# Sheet1.net
KiCad netlist of a schematic drawn in Altium Designer
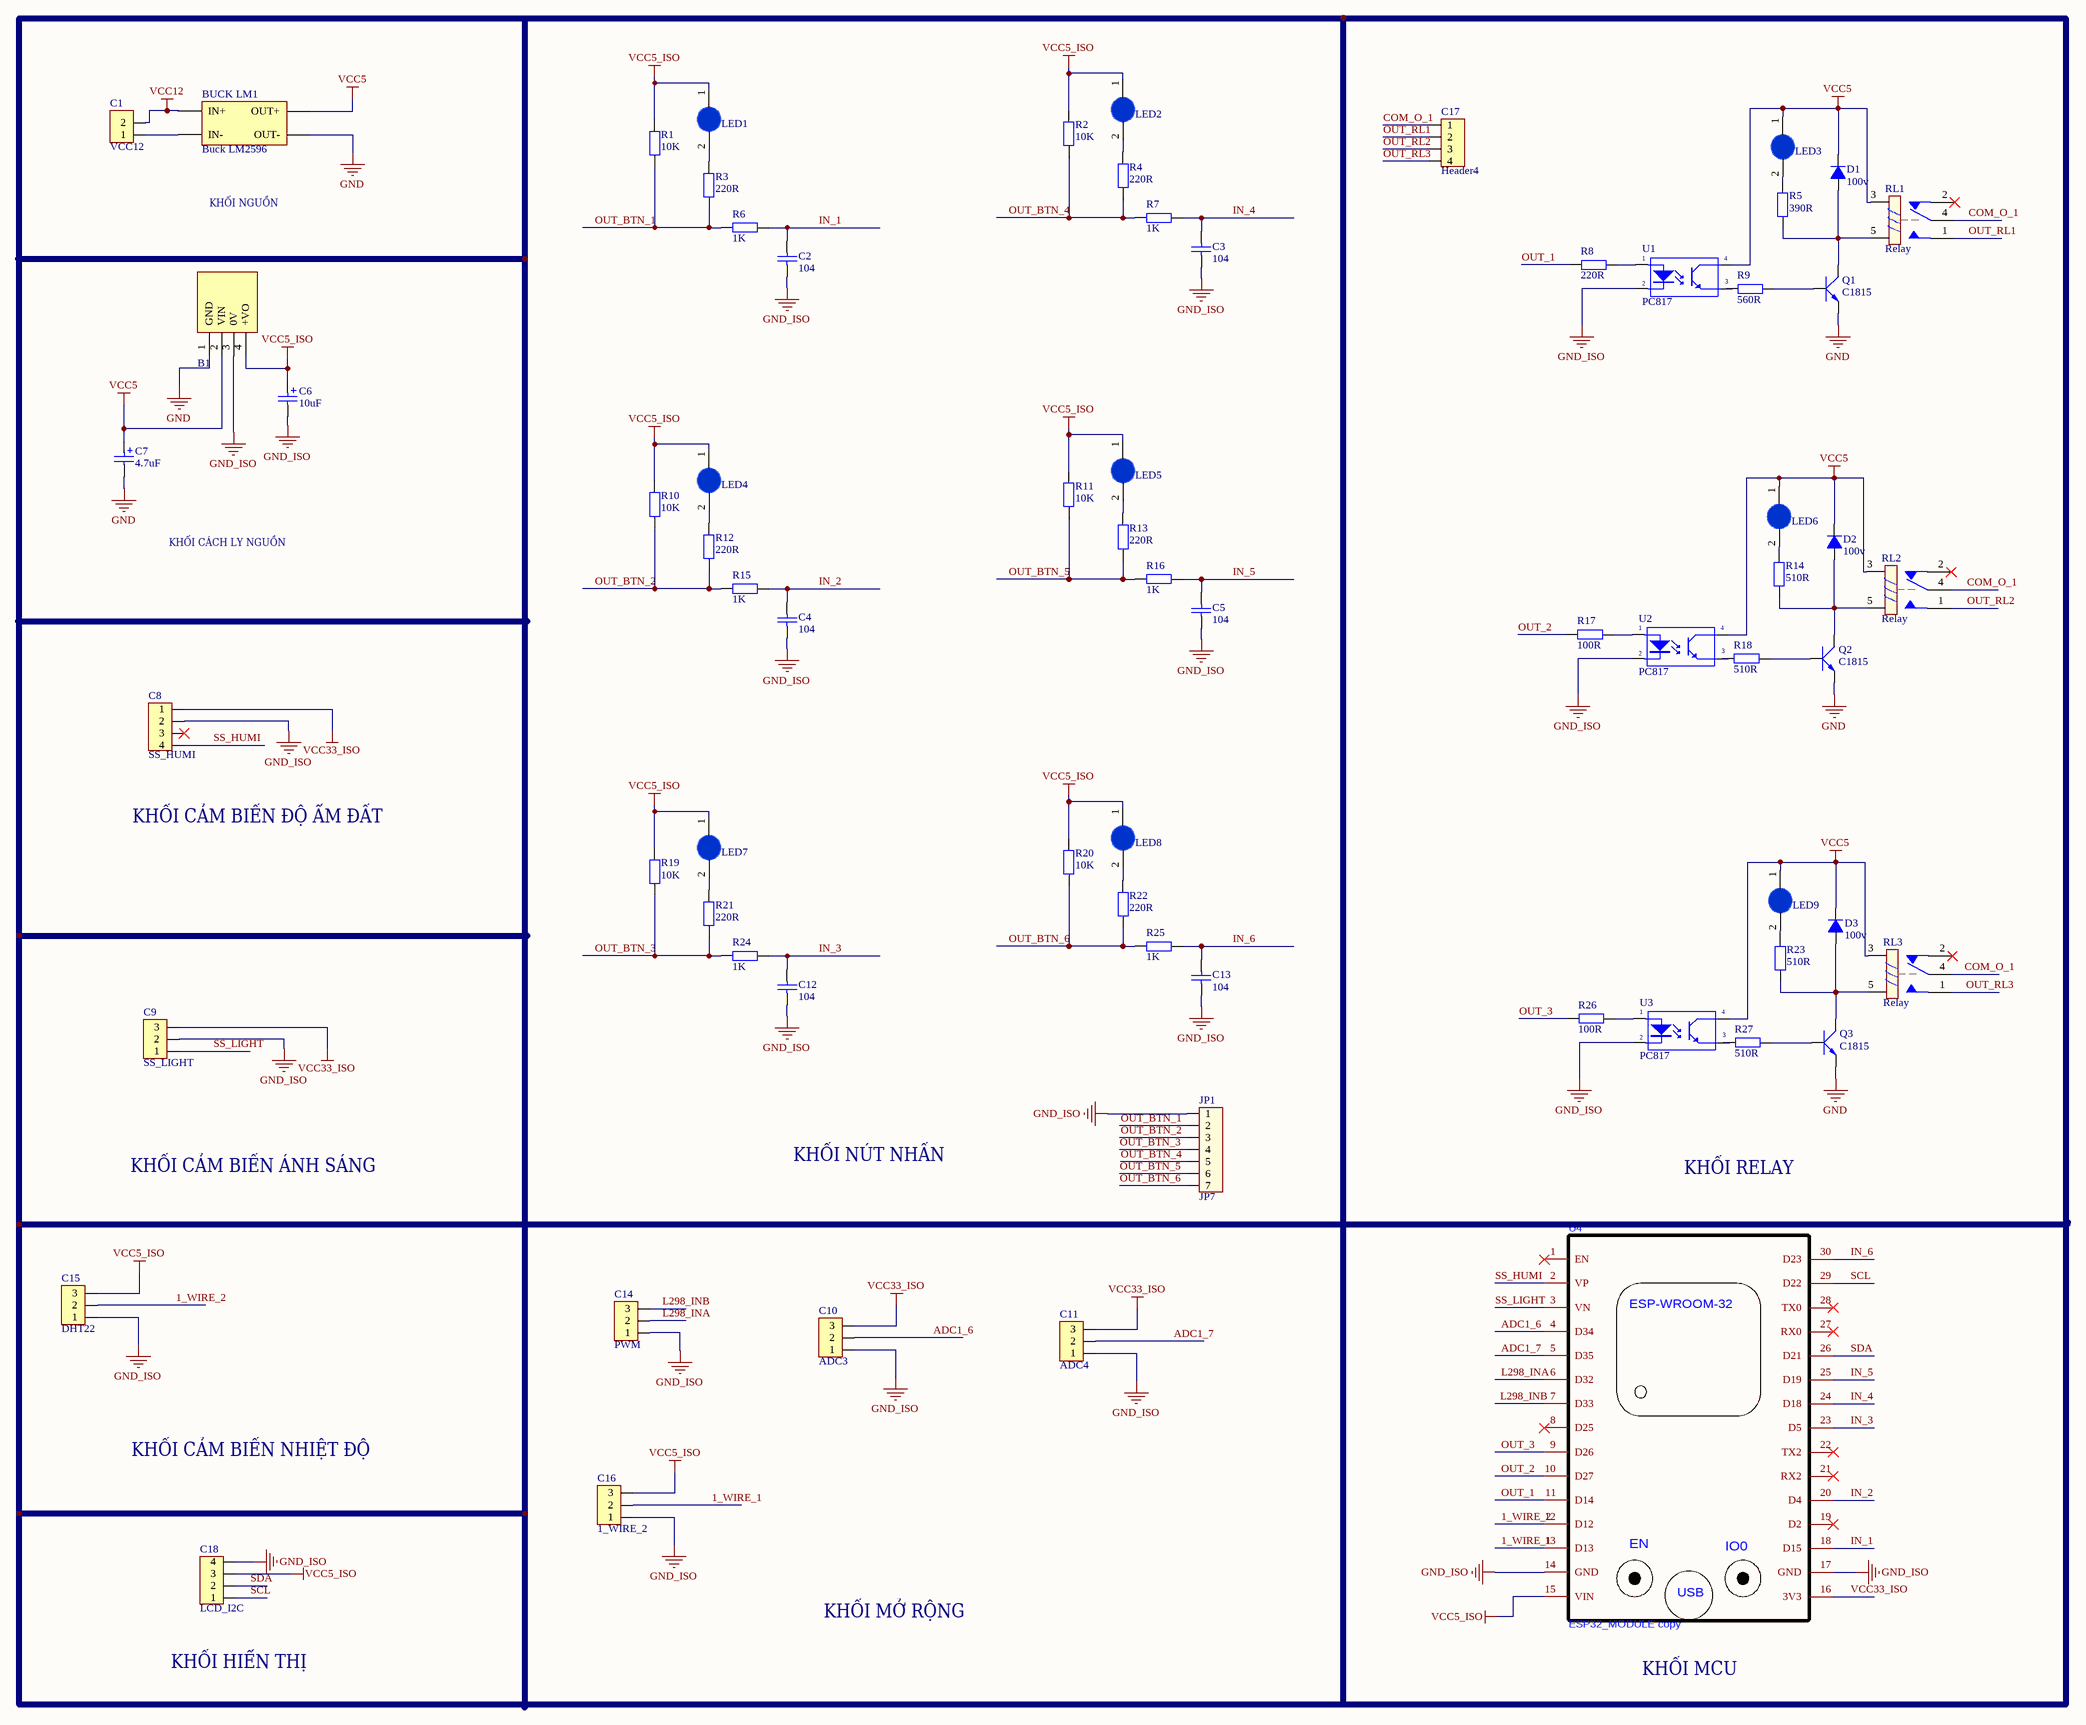
[diagram p0: Sheet1.SchDoc]

(export (version "E")
  (design (tool "Eeschema 10.0.6"))
  (components
    (comp (ref "B1")
      (value "B0505S1W")
      (footprint "B0505S1W")
      (description "Power Supply")
      (fields (field (name "MANUFACTURER_PART_NUMBER") "B0505S-1W"))
      (libsource (lib "myLib_v1") (part "B0505S1W"))
    )
    (comp (ref "BUCK LM1")
      (value "Buck LM2596")
      (footprint "BUCK LM2596")
      (libsource (lib "myLib_v1") (part "Buck LM2596"))
    )
    (comp (ref "C1")
      (value "VCC12")
      (footprint "Header2")
      (description "Header IDC, 2 x 1 Pin Vertical 2.54mm Pitch (Non-Boxed, Male)")
      (fields
        (field (name "MANUFACTURER") "Würth Elektronik eiSos GmbH")
        (field (name "PARTNO") "613002143121")
        (field (name "CREATED BY") "Karrer Zheng")
      )
      (libsource (lib "myLib_v1") (part "Header2"))
    )
    (comp (ref "C2")
      (value "104")
      (footprint "tu gom")
      (description "Cắm")
      (libsource (lib "Altium_Lib_by_KhueNguyenCreator") (part "Tu gom 104 50V"))
    )
    (comp (ref "C3")
      (value "104")
      (footprint "tu gom")
      (description "Cắm")
      (libsource (lib "Altium_Lib_by_KhueNguyenCreator") (part "Tu gom 104 50V"))
    )
    (comp (ref "C4")
      (value "104")
      (footprint "tu gom")
      (description "Cắm")
      (libsource (lib "Altium_Lib_by_KhueNguyenCreator") (part "Tu gom 104 50V"))
    )
    (comp (ref "C5")
      (value "104")
      (footprint "tu gom")
      (description "Cắm")
      (libsource (lib "Altium_Lib_by_KhueNguyenCreator") (part "Tu gom 104 50V"))
    )
    (comp (ref "C6")
      (value "10uF")
      (footprint "CP2/5")
      (description "Polarized Capacitor (Surface Mount)")
      (fields (field (name "Comment") "Cap Pol3") (field (name "PUBLISHER") "Altium Limited"))
      (libsource (lib "myLib_v1") (part "Cap Pol3"))
    )
    (comp (ref "C7")
      (value "4.7uF")
      (footprint "CP2/5")
      (description "Polarized Capacitor (Surface Mount)")
      (fields (field (name "Comment") "Cap Pol3") (field (name "PUBLISHER") "Altium Limited"))
      (libsource (lib "myLib_v1") (part "Cap Pol3"))
    )
    (comp (ref "C8")
      (value "SS_HUMI")
      (footprint "Header4")
      (description "Header IDC, 4 x 1 Pin Vertical 2.54mm Pitch (Non-Boxed, Male)")
      (fields
        (field (name "MANUFACTURER") "Würth Elektronik eiSos GmbH")
        (field (name "PARTNO") "613002143121")
        (field (name "CREATED BY") "Karrer Zheng")
      )
      (libsource (lib "myLib_v1") (part "Header4"))
    )
    (comp (ref "C9")
      (value "SS_LIGHT")
      (footprint "Header3")
      (description "Header IDC, 3 x 1 Pin Vertical 2.54mm Pitch (Non-Boxed, Male)")
      (fields
        (field (name "MANUFACTURER") "Würth Elektronik eiSos GmbH")
        (field (name "PARTNO") "613002143121")
        (field (name "CREATED BY") "Karrer Zheng")
      )
      (libsource (lib "myLib_v1") (part "Header3"))
    )
    (comp (ref "C10")
      (value "ADC3")
      (footprint "Header3")
      (description "Header IDC, 3 x 1 Pin Vertical 2.54mm Pitch (Non-Boxed, Male)")
      (fields
        (field (name "MANUFACTURER") "Würth Elektronik eiSos GmbH")
        (field (name "PARTNO") "613002143121")
        (field (name "CREATED BY") "Karrer Zheng")
      )
      (libsource (lib "myLib_v1") (part "Header3"))
    )
    (comp (ref "C11")
      (value "ADC4")
      (footprint "Header3")
      (description "Header IDC, 3 x 1 Pin Vertical 2.54mm Pitch (Non-Boxed, Male)")
      (fields
        (field (name "MANUFACTURER") "Würth Elektronik eiSos GmbH")
        (field (name "PARTNO") "613002143121")
        (field (name "CREATED BY") "Karrer Zheng")
      )
      (libsource (lib "myLib_v1") (part "Header3"))
    )
    (comp (ref "C12")
      (value "104")
      (footprint "tu gom")
      (description "Cắm")
      (libsource (lib "Altium_Lib_by_KhueNguyenCreator") (part "Tu gom 104 50V"))
    )
    (comp (ref "C13")
      (value "104")
      (footprint "tu gom")
      (description "Cắm")
      (libsource (lib "Altium_Lib_by_KhueNguyenCreator") (part "Tu gom 104 50V"))
    )
    (comp (ref "C14")
      (value "PWM")
      (footprint "Header3")
      (description "Header IDC, 3 x 1 Pin Vertical 2.54mm Pitch (Non-Boxed, Male)")
      (fields
        (field (name "MANUFACTURER") "Würth Elektronik eiSos GmbH")
        (field (name "PARTNO") "613002143121")
        (field (name "CREATED BY") "Karrer Zheng")
      )
      (libsource (lib "myLib_v1") (part "Header3"))
    )
    (comp (ref "C15")
      (value "DHT22")
      (footprint "Header3")
      (description "Header IDC, 3 x 1 Pin Vertical 2.54mm Pitch (Non-Boxed, Male)")
      (fields
        (field (name "MANUFACTURER") "Würth Elektronik eiSos GmbH")
        (field (name "PARTNO") "613002143121")
        (field (name "CREATED BY") "Karrer Zheng")
      )
      (libsource (lib "myLib_v1") (part "Header3"))
    )
    (comp (ref "C16")
      (value "1_WIRE_2")
      (footprint "Header3")
      (description "Header IDC, 3 x 1 Pin Vertical 2.54mm Pitch (Non-Boxed, Male)")
      (fields
        (field (name "MANUFACTURER") "Würth Elektronik eiSos GmbH")
        (field (name "PARTNO") "613002143121")
        (field (name "CREATED BY") "Karrer Zheng")
      )
      (libsource (lib "myLib_v1") (part "Header3"))
    )
    (comp (ref "C17")
      (value "Header4")
      (footprint "Header4")
      (description "Header IDC, 4 x 1 Pin Vertical 2.54mm Pitch (Non-Boxed, Male)")
      (fields
        (field (name "MANUFACTURER") "Würth Elektronik eiSos GmbH")
        (field (name "PARTNO") "613002143121")
        (field (name "CREATED BY") "Karrer Zheng")
      )
      (libsource (lib "") (part "Header4_1"))
    )
    (comp (ref "C18")
      (value "LCD_I2C")
      (footprint "Header4")
      (description "Header IDC, 4 x 1 Pin Vertical 2.54mm Pitch (Non-Boxed, Male)")
      (fields
        (field (name "MANUFACTURER") "Würth Elektronik eiSos GmbH")
        (field (name "PARTNO") "613002143121")
        (field (name "CREATED BY") "Karrer Zheng")
      )
      (libsource (lib "") (part "Header4_2"))
    )
    (comp (ref "D1")
      (value "100v")
      (footprint "DIODE 0.5A")
      (description "Cắm")
      (libsource (lib "Altium_Lib_by_KhueNguyenCreator") (part "Diode 1N4148"))
    )
    (comp (ref "D2")
      (value "100v")
      (footprint "DIODE 0.5A")
      (description "Cắm")
      (libsource (lib "Altium_Lib_by_KhueNguyenCreator") (part "Diode 1N4148"))
    )
    (comp (ref "D3")
      (value "100v")
      (footprint "DIODE 0.5A")
      (description "Cắm")
      (libsource (lib "Altium_Lib_by_KhueNguyenCreator") (part "Diode 1N4148"))
    )
    (comp (ref "JP1")
      (value "JP7")
      (footprint "Header7")
      (description "Connector 7")
      (libsource (lib "myLib_v1") (part "Header7"))
    )
    (comp (ref "LED1")
      (value "LED 3mm")
      (footprint "LED-3MM-BLUE")
      (description "Cắm")
      (libsource (lib "myLib_v1") (part "LED 3mm Xanh Duong"))
    )
    (comp (ref "LED2")
      (value "LED 3mm")
      (footprint "LED-3MM-BLUE")
      (description "Cắm")
      (libsource (lib "myLib_v1") (part "LED 3mm Xanh Duong"))
    )
    (comp (ref "LED3")
      (value "LED 3mm")
      (footprint "LED-3MM-BLUE")
      (description "Cắm")
      (libsource (lib "myLib_v1") (part "LED 3mm Xanh Duong"))
    )
    (comp (ref "LED4")
      (value "LED 3mm")
      (footprint "LED-3MM-BLUE")
      (description "Cắm")
      (libsource (lib "myLib_v1") (part "LED 3mm Xanh Duong"))
    )
    (comp (ref "LED5")
      (value "LED 3mm")
      (footprint "LED-3MM-BLUE")
      (description "Cắm")
      (libsource (lib "myLib_v1") (part "LED 3mm Xanh Duong"))
    )
    (comp (ref "LED6")
      (value "LED 3mm")
      (footprint "LED-3MM-BLUE")
      (description "Cắm")
      (libsource (lib "myLib_v1") (part "LED 3mm Xanh Duong"))
    )
    (comp (ref "LED7")
      (value "LED 3mm")
      (footprint "LED-3MM-BLUE")
      (description "Cắm")
      (libsource (lib "myLib_v1") (part "LED 3mm Xanh Duong"))
    )
    (comp (ref "LED8")
      (value "LED 3mm")
      (footprint "LED-3MM-BLUE")
      (description "Cắm")
      (libsource (lib "myLib_v1") (part "LED 3mm Xanh Duong"))
    )
    (comp (ref "LED9")
      (value "LED 3mm")
      (footprint "LED-3MM-BLUE")
      (description "Cắm")
      (libsource (lib "myLib_v1") (part "LED 3mm Xanh Duong"))
    )
    (comp (ref "Q1")
      (value "C1815")
      (footprint "C1815_cam")
      (description "NPN 600mW, ECB")
      (libsource (lib "myLib_v1") (part "C1815"))
    )
    (comp (ref "Q2")
      (value "C1815")
      (footprint "C1815_cam")
      (description "NPN 600mW, ECB")
      (libsource (lib "myLib_v1") (part "C1815"))
    )
    (comp (ref "Q3")
      (value "C1815")
      (footprint "C1815_cam")
      (description "NPN 600mW, ECB")
      (libsource (lib "myLib_v1") (part "C1815"))
    )
    (comp (ref "R1")
      (value "10K")
      (footprint "R1/4W")
      (description "Resistor 1/4W")
      (libsource (lib "myLib_v1") (part "R1/4W"))
    )
    (comp (ref "R2")
      (value "10K")
      (footprint "R1/4W")
      (description "Resistor 1/4W")
      (libsource (lib "myLib_v1") (part "R1/4W"))
    )
    (comp (ref "R3")
      (value "220R")
      (footprint "R1/4W")
      (description "Resistor 1/4W")
      (libsource (lib "myLib_v1") (part "R1/4W"))
    )
    (comp (ref "R4")
      (value "220R")
      (footprint "R1/4W")
      (description "Resistor 1/4W")
      (libsource (lib "myLib_v1") (part "R1/4W"))
    )
    (comp (ref "R5")
      (value "390R")
      (footprint "R1/4W")
      (description "Resistor 1/4W")
      (libsource (lib "myLib_v1") (part "R1/4W"))
    )
    (comp (ref "R6")
      (value "1K")
      (footprint "R1/4W")
      (description "Resistor 1/4W")
      (libsource (lib "myLib_v1") (part "R1/4W"))
    )
    (comp (ref "R7")
      (value "1K")
      (footprint "R1/4W")
      (description "Resistor 1/4W")
      (libsource (lib "myLib_v1") (part "R1/4W"))
    )
    (comp (ref "R8")
      (value "220R")
      (footprint "R1/4W")
      (description "Resistor 1/4W")
      (libsource (lib "myLib_v1") (part "R1/4W"))
    )
    (comp (ref "R9")
      (value "560R")
      (footprint "R1/4W")
      (description "Resistor 1/4W")
      (libsource (lib "myLib_v1") (part "R1/4W"))
    )
    (comp (ref "R10")
      (value "10K")
      (footprint "R1/4W")
      (description "Resistor 1/4W")
      (libsource (lib "myLib_v1") (part "R1/4W"))
    )
    (comp (ref "R11")
      (value "10K")
      (footprint "R1/4W")
      (description "Resistor 1/4W")
      (libsource (lib "myLib_v1") (part "R1/4W"))
    )
    (comp (ref "R12")
      (value "220R")
      (footprint "R1/4W")
      (description "Resistor 1/4W")
      (libsource (lib "myLib_v1") (part "R1/4W"))
    )
    (comp (ref "R13")
      (value "220R")
      (footprint "R1/4W")
      (description "Resistor 1/4W")
      (libsource (lib "myLib_v1") (part "R1/4W"))
    )
    (comp (ref "R14")
      (value "510R")
      (footprint "R1/4W")
      (description "Resistor 1/4W")
      (libsource (lib "myLib_v1") (part "R1/4W"))
    )
    (comp (ref "R15")
      (value "1K")
      (footprint "R1/4W")
      (description "Resistor 1/4W")
      (libsource (lib "myLib_v1") (part "R1/4W"))
    )
    (comp (ref "R16")
      (value "1K")
      (footprint "R1/4W")
      (description "Resistor 1/4W")
      (libsource (lib "myLib_v1") (part "R1/4W"))
    )
    (comp (ref "R17")
      (value "100R")
      (footprint "R1/4W")
      (description "Resistor 1/4W")
      (libsource (lib "myLib_v1") (part "R1/4W"))
    )
    (comp (ref "R18")
      (value "510R")
      (footprint "R1/4W")
      (description "Resistor 1/4W")
      (libsource (lib "myLib_v1") (part "R1/4W"))
    )
    (comp (ref "R19")
      (value "10K")
      (footprint "R1/4W")
      (description "Resistor 1/4W")
      (libsource (lib "myLib_v1") (part "R1/4W"))
    )
    (comp (ref "R20")
      (value "10K")
      (footprint "R1/4W")
      (description "Resistor 1/4W")
      (libsource (lib "myLib_v1") (part "R1/4W"))
    )
    (comp (ref "R21")
      (value "220R")
      (footprint "R1/4W")
      (description "Resistor 1/4W")
      (libsource (lib "myLib_v1") (part "R1/4W"))
    )
    (comp (ref "R22")
      (value "220R")
      (footprint "R1/4W")
      (description "Resistor 1/4W")
      (libsource (lib "myLib_v1") (part "R1/4W"))
    )
    (comp (ref "R23")
      (value "510R")
      (footprint "R1/4W")
      (description "Resistor 1/4W")
      (libsource (lib "myLib_v1") (part "R1/4W"))
    )
    (comp (ref "R24")
      (value "1K")
      (footprint "R1/4W")
      (description "Resistor 1/4W")
      (libsource (lib "myLib_v1") (part "R1/4W"))
    )
    (comp (ref "R25")
      (value "1K")
      (footprint "R1/4W")
      (description "Resistor 1/4W")
      (libsource (lib "myLib_v1") (part "R1/4W"))
    )
    (comp (ref "R26")
      (value "100R")
      (footprint "R1/4W")
      (description "Resistor 1/4W")
      (libsource (lib "myLib_v1") (part "R1/4W"))
    )
    (comp (ref "R27")
      (value "510R")
      (footprint "R1/4W")
      (description "Resistor 1/4W")
      (libsource (lib "myLib_v1") (part "R1/4W"))
    )
    (comp (ref "RL1")
      (value "Relay")
      (footprint "RELAY_SRA_05VDC_SL_C")
      (description "Relay 5 Chan")
      (libsource (lib "myLib_v1") (part "RL_SRA-05VDC-SL-C"))
    )
    (comp (ref "RL2")
      (value "Relay")
      (footprint "RELAY_SRA_05VDC_SL_C")
      (description "Relay 5 Chan")
      (libsource (lib "myLib_v1") (part "RL_SRA-05VDC-SL-C"))
    )
    (comp (ref "RL3")
      (value "Relay")
      (footprint "RELAY_SRA_05VDC_SL_C")
      (description "Relay 5 Chan")
      (libsource (lib "myLib_v1") (part "RL_SRA-05VDC-SL-C"))
    )
    (comp (ref "U1")
      (value "PC817")
      (footprint "DIP4/W0.3")
      (description "Single Opto")
      (libsource (lib "myLib_v1") (part "PC817"))
    )
    (comp (ref "U2")
      (value "PC817")
      (footprint "DIP4/W0.3")
      (description "Single Opto")
      (libsource (lib "myLib_v1") (part "PC817"))
    )
    (comp (ref "U3")
      (value "PC817")
      (footprint "DIP4/W0.3")
      (description "Single Opto")
      (libsource (lib "myLib_v1") (part "PC817"))
    )
    (comp (ref "U4")
      (value "ESP32_MODULE copy")
      (footprint "ESP32-WIFIMODULE-FOOTPRINT")
      (libsource (lib "myLib_v1") (part "ESP32_MODULE copy"))
    )
  )
  (nets
    (net (code "1") (name "/1_WIRE_1") (class "Default")
      (node (ref "C16") (pin "2") (pinfunction "2_2") (pintype "passive"))
      (node (ref "U4") (pin "13") (pinfunction "D13_13") (pintype "passive"))
    )
    (net (code "2") (name "/1_WIRE_2") (class "Default")
      (node (ref "C15") (pin "2") (pinfunction "2_2") (pintype "passive"))
      (node (ref "U4") (pin "12") (pinfunction "D12_12") (pintype "passive"))
    )
    (net (code "3") (name "/ADC1_6") (class "Default")
      (node (ref "C10") (pin "2") (pinfunction "2_2") (pintype "passive"))
      (node (ref "U4") (pin "4") (pinfunction "D34_4") (pintype "passive"))
    )
    (net (code "4") (name "/ADC1_7") (class "Default")
      (node (ref "C11") (pin "2") (pinfunction "2_2") (pintype "passive"))
      (node (ref "U4") (pin "5") (pinfunction "D35_5") (pintype "passive"))
    )
    (net (code "5") (name "/COM_O_1") (class "Default")
      (node (ref "C17") (pin "1") (pinfunction "1_1") (pintype "passive"))
      (node (ref "RL1") (pin "4") (pinfunction "4_4") (pintype "passive"))
      (node (ref "RL2") (pin "4") (pinfunction "4_4") (pintype "passive"))
      (node (ref "RL3") (pin "4") (pinfunction "4_4") (pintype "passive"))
    )
    (net (code "6") (name "/IN_1") (class "Default")
      (node (ref "C2") (pin "1") (pinfunction "1_1") (pintype "passive"))
      (node (ref "R6") (pin "1") (pinfunction "1_1") (pintype "passive"))
      (node (ref "U4") (pin "18") (pinfunction "D15_18") (pintype "passive"))
    )
    (net (code "7") (name "/IN_2") (class "Default")
      (node (ref "C4") (pin "1") (pinfunction "1_1") (pintype "passive"))
      (node (ref "R15") (pin "1") (pinfunction "1_1") (pintype "passive"))
      (node (ref "U4") (pin "20") (pinfunction "D4_20") (pintype "passive"))
    )
    (net (code "8") (name "/IN_3") (class "Default")
      (node (ref "C12") (pin "1") (pinfunction "1_1") (pintype "passive"))
      (node (ref "R24") (pin "1") (pinfunction "1_1") (pintype "passive"))
      (node (ref "U4") (pin "23") (pinfunction "D5_23") (pintype "passive"))
    )
    (net (code "9") (name "/IN_4") (class "Default")
      (node (ref "C3") (pin "1") (pinfunction "1_1") (pintype "passive"))
      (node (ref "R7") (pin "1") (pinfunction "1_1") (pintype "passive"))
      (node (ref "U4") (pin "24") (pinfunction "D18_24") (pintype "passive"))
    )
    (net (code "10") (name "/IN_5") (class "Default")
      (node (ref "C5") (pin "1") (pinfunction "1_1") (pintype "passive"))
      (node (ref "R16") (pin "1") (pinfunction "1_1") (pintype "passive"))
      (node (ref "U4") (pin "25") (pinfunction "D19_25") (pintype "passive"))
    )
    (net (code "11") (name "/IN_6") (class "Default")
      (node (ref "C13") (pin "1") (pinfunction "1_1") (pintype "passive"))
      (node (ref "R25") (pin "1") (pinfunction "1_1") (pintype "passive"))
      (node (ref "U4") (pin "30") (pinfunction "D23_30") (pintype "passive"))
    )
    (net (code "12") (name "/L298_INA") (class "Default")
      (node (ref "C14") (pin "2") (pinfunction "2_2") (pintype "passive"))
      (node (ref "U4") (pin "6") (pinfunction "D32_6") (pintype "passive"))
    )
    (net (code "13") (name "/L298_INB") (class "Default")
      (node (ref "C14") (pin "3") (pinfunction "3_3") (pintype "passive"))
      (node (ref "U4") (pin "7") (pinfunction "D33_7") (pintype "passive"))
    )
    (net (code "14") (name "/OUT_1") (class "Default")
      (node (ref "R8") (pin "1") (pinfunction "1_1") (pintype "passive"))
      (node (ref "U4") (pin "11") (pinfunction "D14_11") (pintype "passive"))
    )
    (net (code "15") (name "/OUT_2") (class "Default")
      (node (ref "R17") (pin "1") (pinfunction "1_1") (pintype "passive"))
      (node (ref "U4") (pin "10") (pinfunction "D27_10") (pintype "passive"))
    )
    (net (code "16") (name "/OUT_3") (class "Default")
      (node (ref "R26") (pin "1") (pinfunction "1_1") (pintype "passive"))
      (node (ref "U4") (pin "9") (pinfunction "D26_9") (pintype "passive"))
    )
    (net (code "17") (name "/OUT_BTN_1") (class "Default")
      (node (ref "JP1") (pin "2") (pinfunction "2_2") (pintype "passive"))
      (node (ref "R1") (pin "1") (pinfunction "1_1") (pintype "passive"))
      (node (ref "R3") (pin "1") (pinfunction "1_1") (pintype "passive"))
      (node (ref "R6") (pin "2") (pinfunction "2_2") (pintype "passive"))
    )
    (net (code "18") (name "/OUT_BTN_2") (class "Default")
      (node (ref "JP1") (pin "3") (pinfunction "3_3") (pintype "passive"))
      (node (ref "R10") (pin "1") (pinfunction "1_1") (pintype "passive"))
      (node (ref "R12") (pin "1") (pinfunction "1_1") (pintype "passive"))
      (node (ref "R15") (pin "2") (pinfunction "2_2") (pintype "passive"))
    )
    (net (code "19") (name "/OUT_BTN_3") (class "Default")
      (node (ref "JP1") (pin "4") (pinfunction "4_4") (pintype "passive"))
      (node (ref "R19") (pin "1") (pinfunction "1_1") (pintype "passive"))
      (node (ref "R21") (pin "1") (pinfunction "1_1") (pintype "passive"))
      (node (ref "R24") (pin "2") (pinfunction "2_2") (pintype "passive"))
    )
    (net (code "20") (name "/OUT_BTN_4") (class "Default")
      (node (ref "JP1") (pin "5") (pinfunction "5_5") (pintype "passive"))
      (node (ref "R2") (pin "1") (pinfunction "1_1") (pintype "passive"))
      (node (ref "R4") (pin "1") (pinfunction "1_1") (pintype "passive"))
      (node (ref "R7") (pin "2") (pinfunction "2_2") (pintype "passive"))
    )
    (net (code "21") (name "/OUT_BTN_5") (class "Default")
      (node (ref "JP1") (pin "6") (pinfunction "6_6") (pintype "passive"))
      (node (ref "R11") (pin "1") (pinfunction "1_1") (pintype "passive"))
      (node (ref "R13") (pin "1") (pinfunction "1_1") (pintype "passive"))
      (node (ref "R16") (pin "2") (pinfunction "2_2") (pintype "passive"))
    )
    (net (code "22") (name "/OUT_BTN_6") (class "Default")
      (node (ref "JP1") (pin "7") (pinfunction "7_7") (pintype "passive"))
      (node (ref "R20") (pin "1") (pinfunction "1_1") (pintype "passive"))
      (node (ref "R22") (pin "1") (pinfunction "1_1") (pintype "passive"))
      (node (ref "R25") (pin "2") (pinfunction "2_2") (pintype "passive"))
    )
    (net (code "23") (name "/OUT_RL1") (class "Default")
      (node (ref "C17") (pin "2") (pinfunction "2_2") (pintype "passive"))
      (node (ref "RL1") (pin "1") (pinfunction "1_1") (pintype "passive"))
    )
    (net (code "24") (name "/OUT_RL2") (class "Default")
      (node (ref "C17") (pin "3") (pinfunction "3_3") (pintype "passive"))
      (node (ref "RL2") (pin "1") (pinfunction "1_1") (pintype "passive"))
    )
    (net (code "25") (name "/OUT_RL3") (class "Default")
      (node (ref "C17") (pin "4") (pinfunction "4_4") (pintype "passive"))
      (node (ref "RL3") (pin "1") (pinfunction "1_1") (pintype "passive"))
    )
    (net (code "26") (name "/SCL") (class "Default")
      (node (ref "C18") (pin "1") (pinfunction "1_1") (pintype "passive"))
      (node (ref "U4") (pin "29") (pinfunction "D22_29") (pintype "passive"))
    )
    (net (code "27") (name "/SDA") (class "Default")
      (node (ref "C18") (pin "2") (pinfunction "2_2") (pintype "passive"))
      (node (ref "U4") (pin "26") (pinfunction "D21_26") (pintype "passive"))
    )
    (net (code "28") (name "/SS_HUMI") (class "Default")
      (node (ref "C8") (pin "4") (pinfunction "4_4") (pintype "passive"))
      (node (ref "U4") (pin "2") (pinfunction "VP_2") (pintype "passive"))
    )
    (net (code "29") (name "/SS_LIGHT") (class "Default")
      (node (ref "C9") (pin "1") (pinfunction "1_1") (pintype "passive"))
      (node (ref "U4") (pin "3") (pinfunction "VN_3") (pintype "passive"))
    )
    (net (code "30") (name "GND") (class "Default")
      (node (ref "B1") (pin "1") (pinfunction "GND_1") (pintype "passive"))
      (node (ref "BUCK LM1") (pin "3") (pinfunction "OUT-_3") (pintype "passive"))
      (node (ref "C7") (pin "2") (pinfunction "2_2") (pintype "passive"))
      (node (ref "Q1") (pin "1") (pinfunction "E_1") (pintype "passive"))
      (node (ref "Q2") (pin "1") (pinfunction "E_1") (pintype "passive"))
      (node (ref "Q3") (pin "1") (pinfunction "E_1") (pintype "passive"))
    )
    (net (code "31") (name "GND_ISO") (class "Default")
      (node (ref "B1") (pin "3") (pinfunction "0V_3") (pintype "passive"))
      (node (ref "C10") (pin "1") (pinfunction "1_1") (pintype "passive"))
      (node (ref "C11") (pin "1") (pinfunction "1_1") (pintype "passive"))
      (node (ref "C12") (pin "2") (pinfunction "2_2") (pintype "passive"))
      (node (ref "C13") (pin "2") (pinfunction "2_2") (pintype "passive"))
      (node (ref "C14") (pin "1") (pinfunction "1_1") (pintype "passive"))
      (node (ref "C15") (pin "1") (pinfunction "1_1") (pintype "passive"))
      (node (ref "C16") (pin "1") (pinfunction "1_1") (pintype "passive"))
      (node (ref "C18") (pin "4") (pinfunction "4_4") (pintype "passive"))
      (node (ref "C2") (pin "2") (pinfunction "2_2") (pintype "passive"))
      (node (ref "C3") (pin "2") (pinfunction "2_2") (pintype "passive"))
      (node (ref "C4") (pin "2") (pinfunction "2_2") (pintype "passive"))
      (node (ref "C5") (pin "2") (pinfunction "2_2") (pintype "passive"))
      (node (ref "C6") (pin "2") (pinfunction "2_2") (pintype "passive"))
      (node (ref "C8") (pin "2") (pinfunction "2_2") (pintype "passive"))
      (node (ref "C9") (pin "2") (pinfunction "2_2") (pintype "passive"))
      (node (ref "JP1") (pin "1") (pinfunction "1_1") (pintype "passive"))
      (node (ref "U1") (pin "2") (pinfunction "K_2") (pintype "passive"))
      (node (ref "U2") (pin "2") (pinfunction "K_2") (pintype "passive"))
      (node (ref "U3") (pin "2") (pinfunction "K_2") (pintype "passive"))
      (node (ref "U4") (pin "14") (pinfunction "GND_14") (pintype "passive"))
      (node (ref "U4") (pin "17") (pinfunction "GND_17") (pintype "passive"))
    )
    (net (code "32") (name "Net-(BUCK LM1-IN-)") (class "Default")
      (node (ref "BUCK LM1") (pin "2") (pinfunction "IN-_2") (pintype "passive"))
      (node (ref "C1") (pin "1") (pinfunction "1_1") (pintype "passive"))
    )
    (net (code "33") (name "Net-(D1-A)") (class "Default")
      (node (ref "D1") (pin "1") (pinfunction "A_1") (pintype "passive"))
      (node (ref "Q1") (pin "2") (pinfunction "C_2") (pintype "passive"))
      (node (ref "R5") (pin "2") (pinfunction "2_2") (pintype "passive"))
      (node (ref "RL1") (pin "5") (pinfunction "5_5") (pintype "passive"))
    )
    (net (code "34") (name "Net-(D2-A)") (class "Default")
      (node (ref "D2") (pin "1") (pinfunction "A_1") (pintype "passive"))
      (node (ref "Q2") (pin "2") (pinfunction "C_2") (pintype "passive"))
      (node (ref "R14") (pin "2") (pinfunction "2_2") (pintype "passive"))
      (node (ref "RL2") (pin "5") (pinfunction "5_5") (pintype "passive"))
    )
    (net (code "35") (name "Net-(D3-A)") (class "Default")
      (node (ref "D3") (pin "1") (pinfunction "A_1") (pintype "passive"))
      (node (ref "Q3") (pin "2") (pinfunction "C_2") (pintype "passive"))
      (node (ref "R23") (pin "2") (pinfunction "2_2") (pintype "passive"))
      (node (ref "RL3") (pin "5") (pinfunction "5_5") (pintype "passive"))
    )
    (net (code "36") (name "Net-(LED1-K)") (class "Default")
      (node (ref "LED1") (pin "2") (pinfunction "K_2") (pintype "passive"))
      (node (ref "R3") (pin "2") (pinfunction "2_2") (pintype "passive"))
    )
    (net (code "37") (name "Net-(LED2-K)") (class "Default")
      (node (ref "LED2") (pin "2") (pinfunction "K_2") (pintype "passive"))
      (node (ref "R4") (pin "2") (pinfunction "2_2") (pintype "passive"))
    )
    (net (code "38") (name "Net-(LED3-K)") (class "Default")
      (node (ref "LED3") (pin "2") (pinfunction "K_2") (pintype "passive"))
      (node (ref "R5") (pin "1") (pinfunction "1_1") (pintype "passive"))
    )
    (net (code "39") (name "Net-(LED4-K)") (class "Default")
      (node (ref "LED4") (pin "2") (pinfunction "K_2") (pintype "passive"))
      (node (ref "R12") (pin "2") (pinfunction "2_2") (pintype "passive"))
    )
    (net (code "40") (name "Net-(LED5-K)") (class "Default")
      (node (ref "LED5") (pin "2") (pinfunction "K_2") (pintype "passive"))
      (node (ref "R13") (pin "2") (pinfunction "2_2") (pintype "passive"))
    )
    (net (code "41") (name "Net-(LED6-K)") (class "Default")
      (node (ref "LED6") (pin "2") (pinfunction "K_2") (pintype "passive"))
      (node (ref "R14") (pin "1") (pinfunction "1_1") (pintype "passive"))
    )
    (net (code "42") (name "Net-(LED7-K)") (class "Default")
      (node (ref "LED7") (pin "2") (pinfunction "K_2") (pintype "passive"))
      (node (ref "R21") (pin "2") (pinfunction "2_2") (pintype "passive"))
    )
    (net (code "43") (name "Net-(LED8-K)") (class "Default")
      (node (ref "LED8") (pin "2") (pinfunction "K_2") (pintype "passive"))
      (node (ref "R22") (pin "2") (pinfunction "2_2") (pintype "passive"))
    )
    (net (code "44") (name "Net-(LED9-K)") (class "Default")
      (node (ref "LED9") (pin "2") (pinfunction "K_2") (pintype "passive"))
      (node (ref "R23") (pin "1") (pinfunction "1_1") (pintype "passive"))
    )
    (net (code "45") (name "Net-(Q1-B)") (class "Default")
      (node (ref "Q1") (pin "3") (pinfunction "B_3") (pintype "passive"))
      (node (ref "R9") (pin "2") (pinfunction "2_2") (pintype "passive"))
    )
    (net (code "46") (name "Net-(Q2-B)") (class "Default")
      (node (ref "Q2") (pin "3") (pinfunction "B_3") (pintype "passive"))
      (node (ref "R18") (pin "2") (pinfunction "2_2") (pintype "passive"))
    )
    (net (code "47") (name "Net-(Q3-B)") (class "Default")
      (node (ref "Q3") (pin "3") (pinfunction "B_3") (pintype "passive"))
      (node (ref "R27") (pin "2") (pinfunction "2_2") (pintype "passive"))
    )
    (net (code "48") (name "Net-(U1-A)") (class "Default")
      (node (ref "R8") (pin "2") (pinfunction "2_2") (pintype "passive"))
      (node (ref "U1") (pin "1") (pinfunction "A_1") (pintype "passive"))
    )
    (net (code "49") (name "Net-(U1-E)") (class "Default")
      (node (ref "R9") (pin "1") (pinfunction "1_1") (pintype "passive"))
      (node (ref "U1") (pin "3") (pinfunction "E_3") (pintype "passive"))
    )
    (net (code "50") (name "Net-(U2-A)") (class "Default")
      (node (ref "R17") (pin "2") (pinfunction "2_2") (pintype "passive"))
      (node (ref "U2") (pin "1") (pinfunction "A_1") (pintype "passive"))
    )
    (net (code "51") (name "Net-(U2-E)") (class "Default")
      (node (ref "R18") (pin "1") (pinfunction "1_1") (pintype "passive"))
      (node (ref "U2") (pin "3") (pinfunction "E_3") (pintype "passive"))
    )
    (net (code "52") (name "Net-(U3-A)") (class "Default")
      (node (ref "R26") (pin "2") (pinfunction "2_2") (pintype "passive"))
      (node (ref "U3") (pin "1") (pinfunction "A_1") (pintype "passive"))
    )
    (net (code "53") (name "Net-(U3-E)") (class "Default")
      (node (ref "R27") (pin "1") (pinfunction "1_1") (pintype "passive"))
      (node (ref "U3") (pin "3") (pinfunction "E_3") (pintype "passive"))
    )
    (net (code "54") (name "VCC5") (class "Default")
      (node (ref "B1") (pin "2") (pinfunction "VIN_2") (pintype "passive"))
      (node (ref "BUCK LM1") (pin "4") (pinfunction "OUT+_4") (pintype "passive"))
      (node (ref "C7") (pin "1") (pinfunction "1_1") (pintype "passive"))
      (node (ref "D1") (pin "2") (pinfunction "K_2") (pintype "passive"))
      (node (ref "D2") (pin "2") (pinfunction "K_2") (pintype "passive"))
      (node (ref "D3") (pin "2") (pinfunction "K_2") (pintype "passive"))
      (node (ref "LED3") (pin "1") (pinfunction "A_1") (pintype "passive"))
      (node (ref "LED6") (pin "1") (pinfunction "A_1") (pintype "passive"))
      (node (ref "LED9") (pin "1") (pinfunction "A_1") (pintype "passive"))
      (node (ref "RL1") (pin "3") (pinfunction "3_3") (pintype "passive"))
      (node (ref "RL2") (pin "3") (pinfunction "3_3") (pintype "passive"))
      (node (ref "RL3") (pin "3") (pinfunction "3_3") (pintype "passive"))
      (node (ref "U1") (pin "4") (pinfunction "C_4") (pintype "passive"))
      (node (ref "U2") (pin "4") (pinfunction "C_4") (pintype "passive"))
      (node (ref "U3") (pin "4") (pinfunction "C_4") (pintype "passive"))
    )
    (net (code "55") (name "VCC5_ISO") (class "Default")
      (node (ref "B1") (pin "4") (pinfunction "+VO_4") (pintype "passive"))
      (node (ref "C15") (pin "3") (pinfunction "3_3") (pintype "passive"))
      (node (ref "C16") (pin "3") (pinfunction "3_3") (pintype "passive"))
      (node (ref "C18") (pin "3") (pinfunction "3_3") (pintype "passive"))
      (node (ref "C6") (pin "1") (pinfunction "1_1") (pintype "passive"))
      (node (ref "LED1") (pin "1") (pinfunction "A_1") (pintype "passive"))
      (node (ref "LED2") (pin "1") (pinfunction "A_1") (pintype "passive"))
      (node (ref "LED4") (pin "1") (pinfunction "A_1") (pintype "passive"))
      (node (ref "LED5") (pin "1") (pinfunction "A_1") (pintype "passive"))
      (node (ref "LED7") (pin "1") (pinfunction "A_1") (pintype "passive"))
      (node (ref "LED8") (pin "1") (pinfunction "A_1") (pintype "passive"))
      (node (ref "R1") (pin "2") (pinfunction "2_2") (pintype "passive"))
      (node (ref "R10") (pin "2") (pinfunction "2_2") (pintype "passive"))
      (node (ref "R11") (pin "2") (pinfunction "2_2") (pintype "passive"))
      (node (ref "R19") (pin "2") (pinfunction "2_2") (pintype "passive"))
      (node (ref "R2") (pin "2") (pinfunction "2_2") (pintype "passive"))
      (node (ref "R20") (pin "2") (pinfunction "2_2") (pintype "passive"))
      (node (ref "U4") (pin "15") (pinfunction "VIN_15") (pintype "passive"))
    )
    (net (code "56") (name "VCC12") (class "Default")
      (node (ref "BUCK LM1") (pin "1") (pinfunction "IN+_1") (pintype "passive"))
      (node (ref "C1") (pin "2") (pinfunction "2_2") (pintype "passive"))
    )
    (net (code "57") (name "VCC33_ISO") (class "Default")
      (node (ref "C10") (pin "3") (pinfunction "3_3") (pintype "passive"))
      (node (ref "C11") (pin "3") (pinfunction "3_3") (pintype "passive"))
      (node (ref "C8") (pin "1") (pinfunction "1_1") (pintype "passive"))
      (node (ref "C9") (pin "3") (pinfunction "3_3") (pintype "passive"))
      (node (ref "U4") (pin "16") (pinfunction "3V3_16") (pintype "passive"))
    )
    (net (code "58") (name "unconnected-(C8-Pad3)") (class "Default")
      (node (ref "C8") (pin "3") (pinfunction "3_3") (pintype "passive+no_connect"))
    )
    (net (code "59") (name "unconnected-(RL1-Pad2)") (class "Default")
      (node (ref "RL1") (pin "2") (pinfunction "2_2") (pintype "passive+no_connect"))
    )
    (net (code "60") (name "unconnected-(RL2-Pad2)") (class "Default")
      (node (ref "RL2") (pin "2") (pinfunction "2_2") (pintype "passive+no_connect"))
    )
    (net (code "61") (name "unconnected-(RL3-Pad2)") (class "Default")
      (node (ref "RL3") (pin "2") (pinfunction "2_2") (pintype "passive+no_connect"))
    )
    (net (code "62") (name "unconnected-(U4-D2-Pad19)") (class "Default")
      (node (ref "U4") (pin "19") (pinfunction "D2_19") (pintype "passive+no_connect"))
    )
    (net (code "63") (name "unconnected-(U4-D25-Pad8)") (class "Default")
      (node (ref "U4") (pin "8") (pinfunction "D25_8") (pintype "passive+no_connect"))
    )
    (net (code "64") (name "unconnected-(U4-EN-Pad1)") (class "Default")
      (node (ref "U4") (pin "1") (pinfunction "EN_1") (pintype "passive+no_connect"))
    )
    (net (code "65") (name "unconnected-(U4-RX0-Pad27)") (class "Default")
      (node (ref "U4") (pin "27") (pinfunction "RX0_27") (pintype "passive+no_connect"))
    )
    (net (code "66") (name "unconnected-(U4-RX2-Pad21)") (class "Default")
      (node (ref "U4") (pin "21") (pinfunction "RX2_21") (pintype "passive+no_connect"))
    )
    (net (code "67") (name "unconnected-(U4-TX0-Pad28)") (class "Default")
      (node (ref "U4") (pin "28") (pinfunction "TX0_28") (pintype "passive+no_connect"))
    )
    (net (code "68") (name "unconnected-(U4-TX2-Pad22)") (class "Default")
      (node (ref "U4") (pin "22") (pinfunction "TX2_22") (pintype "passive+no_connect"))
    )
  )
)
